# Power_Suppy_Schematic.net
KiCad netlist of a schematic drawn in Altium Designer
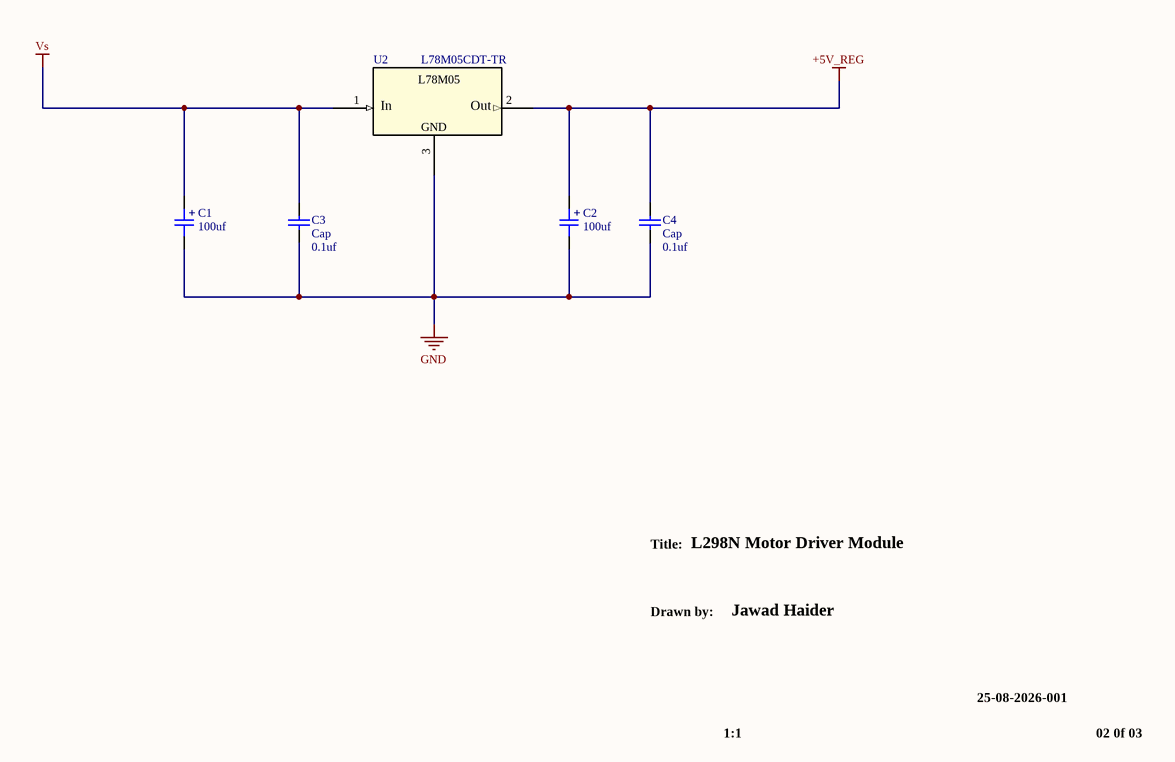
[diagram p0: Power Suppy Schematic.SchDoc]

(export (version "E")
  (design (tool "Eeschema 10.0.6"))
  (components
    (comp (ref "C1")
      (value "100uf")
      (footprint "CAP_AE_SMD_D6MM3_H5M55")
      (description "Capacitor SMD Aluminium Electrolytic 6.3mm Diameter 5.5mm Height")
      (libsource (lib "Schematic-Lib-PhilsLab") (part "CAP_ALEL_6.3x5.5"))
    )
    (comp (ref "C2")
      (value "100uf")
      (footprint "CAP_AE_SMD_D6MM3_H5M55")
      (description "Capacitor SMD Aluminium Electrolytic 6.3mm Diameter 5.5mm Height")
      (libsource (lib "Schematic-Lib-PhilsLab") (part "CAP_ALEL_6.3x5.5"))
    )
    (comp (ref "C3")
      (value "Cap")
      (footprint "CAP_0603")
      (description "Capacitor")
      (fields (field (name "ALTIUM_VALUE") "0.1uf") (field (name "PUBLISHER") "Altium Limited"))
      (libsource (lib "Miscellaneous Devices") (part "Cap"))
    )
    (comp (ref "C4")
      (value "Cap")
      (footprint "CAP_0603")
      (description "Capacitor")
      (fields (field (name "ALTIUM_VALUE") "0.1uf") (field (name "PUBLISHER") "Altium Limited"))
      (libsource (lib "Miscellaneous Devices") (part "Cap"))
    )
    (comp (ref "U2")
      (value "L78M05CDT-TR")
      (footprint "DPAK_STM")
      (description "Precision 500 mA regulators")
      (fields (field (name "COPYRIGHT") "Copyright (C) 2025 Ultra Librarian. All rights reserved."))
      (libsource (lib "L78M05CDT-TR") (part "L78M05CDT-TR"))
    )
  )
  (nets
    (net (code "1") (name "+5V_REG") (class "Default")
      (node (ref "C2") (pin "1") (pinfunction "1_1") (pintype "passive"))
      (node (ref "C4") (pin "2") (pinfunction "2_2") (pintype "passive"))
      (node (ref "U2") (pin "2") (pinfunction "OUTPUT_2") (pintype "output"))
    )
    (net (code "2") (name "GND") (class "Default")
      (node (ref "C1") (pin "2") (pinfunction "2_2") (pintype "passive"))
      (node (ref "C2") (pin "2") (pinfunction "2_2") (pintype "passive"))
      (node (ref "C3") (pin "1") (pinfunction "1_1") (pintype "passive"))
      (node (ref "C4") (pin "1") (pinfunction "1_1") (pintype "passive"))
      (node (ref "U2") (pin "3") (pinfunction "GROUND_3") (pintype "power_in"))
    )
    (net (code "3") (name "Vs") (class "Default")
      (node (ref "C1") (pin "1") (pinfunction "1_1") (pintype "passive"))
      (node (ref "C3") (pin "2") (pinfunction "2_2") (pintype "passive"))
      (node (ref "U2") (pin "1") (pinfunction "INPUT_1") (pintype "input"))
    )
  )
)
